# protoslice.net
KiCad netlist of a schematic drawn in EAGLE
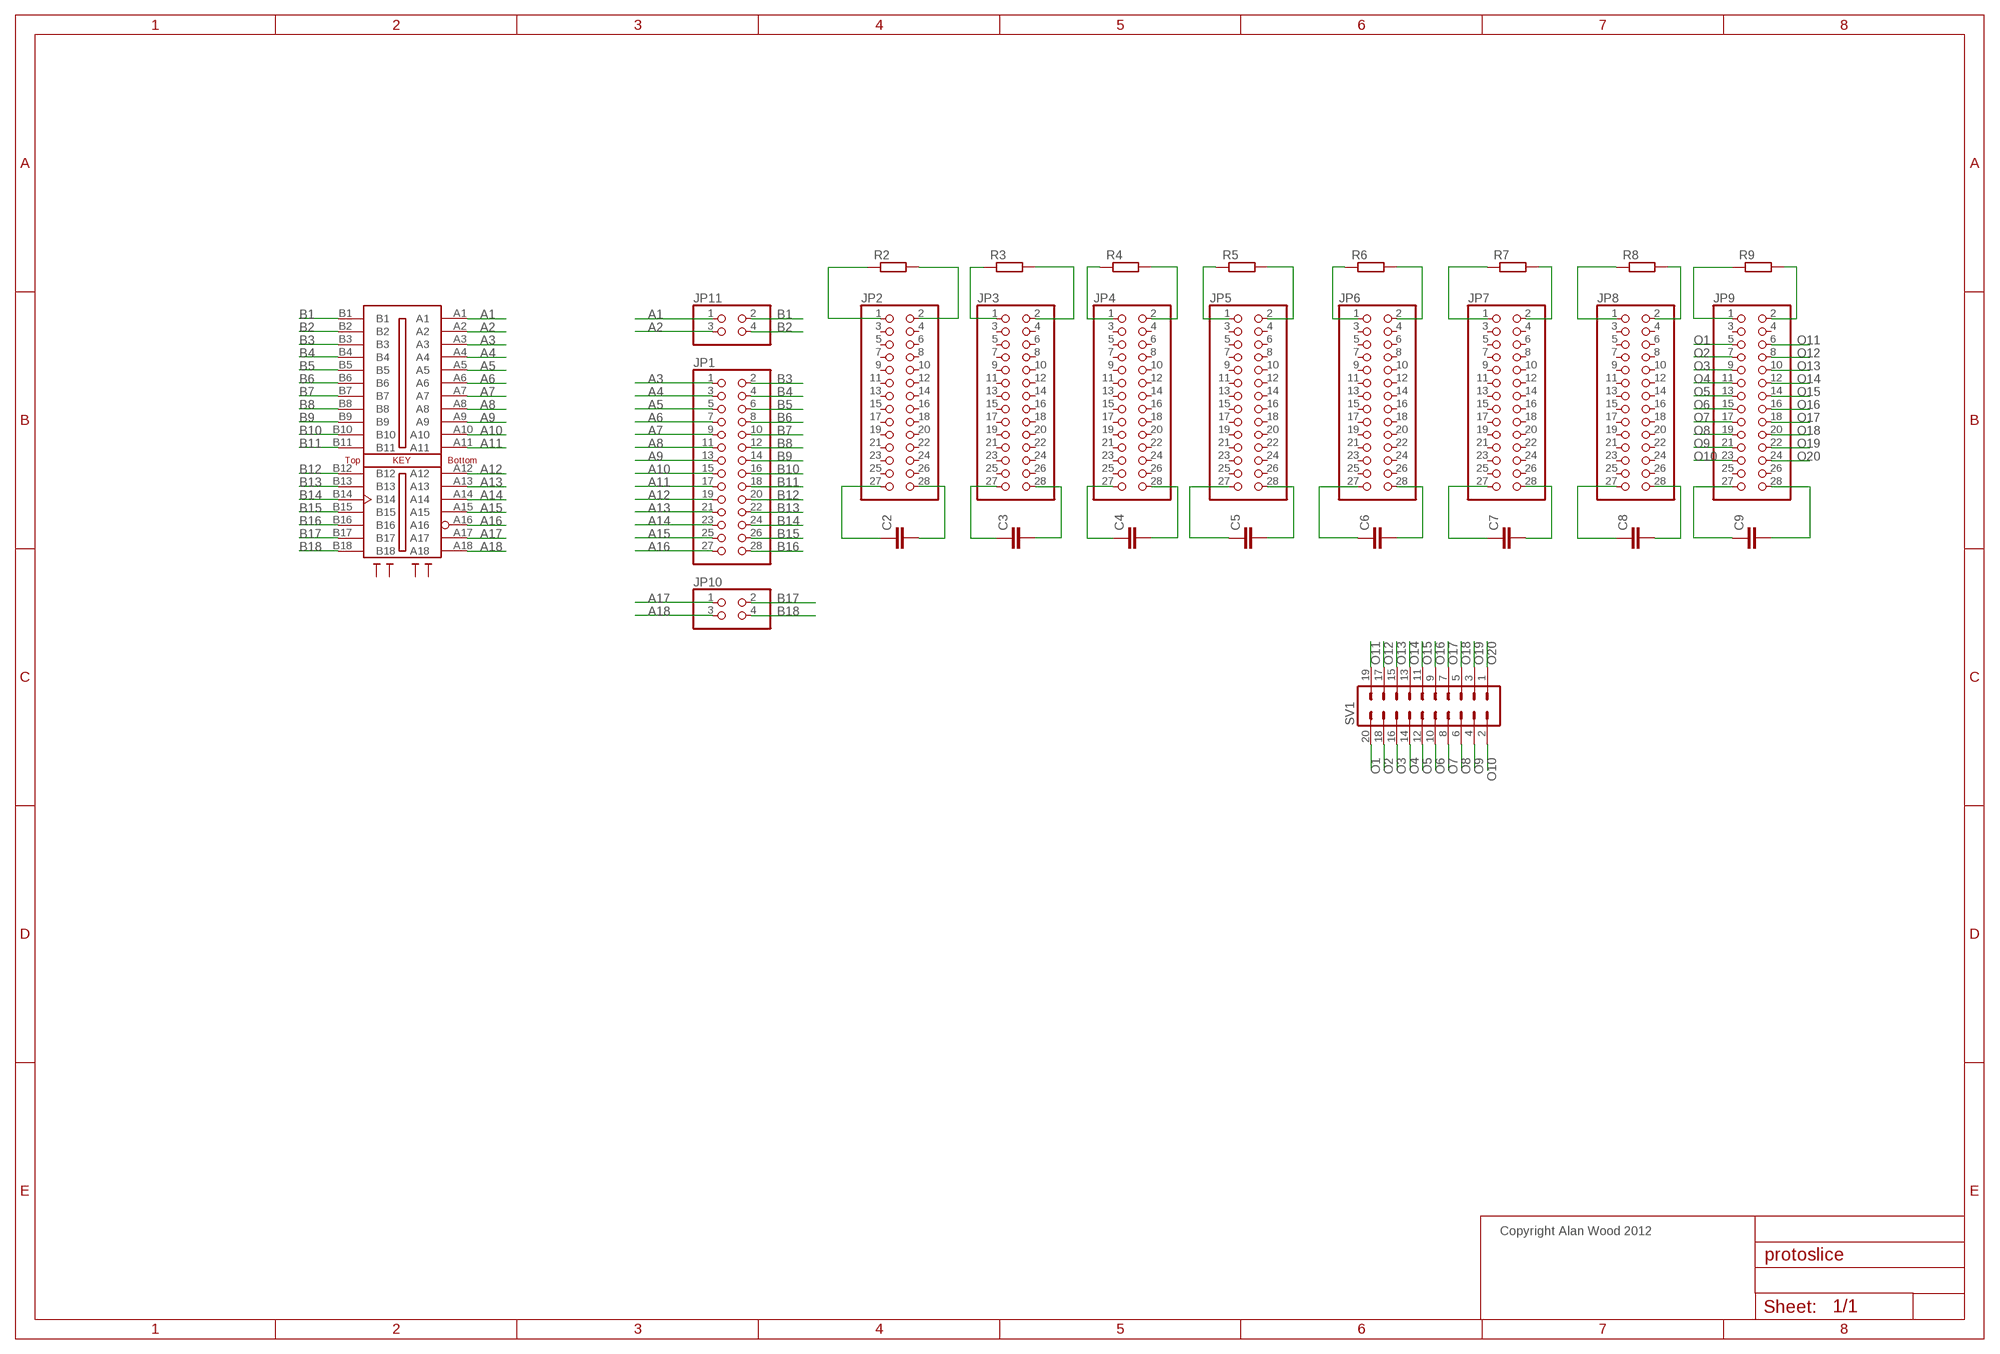
[diagram p0: schematic, sheet 1]

(export (version "E")
  (design (tool "Eeschema 10.0.6"))
  (components
    (comp (ref "C2")
      (value "C-EUC0805")
      (footprint "eagle-import:C0805")
      (libsource (lib "eagle-import") (part "C-EUC0805"))
    )
    (comp (ref "C3")
      (value "C-EUC0805")
      (footprint "eagle-import:C0805")
      (libsource (lib "eagle-import") (part "C-EUC0805"))
    )
    (comp (ref "C4")
      (value "C-EUC0805")
      (footprint "eagle-import:C0805")
      (libsource (lib "eagle-import") (part "C-EUC0805"))
    )
    (comp (ref "C5")
      (value "C-EUC0805")
      (footprint "eagle-import:C0805")
      (libsource (lib "eagle-import") (part "C-EUC0805"))
    )
    (comp (ref "C6")
      (value "C-EUC0805")
      (footprint "eagle-import:C0805")
      (libsource (lib "eagle-import") (part "C-EUC0805"))
    )
    (comp (ref "C7")
      (value "C-EUC0805")
      (footprint "eagle-import:C0805")
      (libsource (lib "eagle-import") (part "C-EUC0805"))
    )
    (comp (ref "C8")
      (value "C-EUC0805")
      (footprint "eagle-import:C0805")
      (libsource (lib "eagle-import") (part "C-EUC0805"))
    )
    (comp (ref "C9")
      (value "C-EUC0805")
      (footprint "eagle-import:C0805")
      (libsource (lib "eagle-import") (part "C-EUC0805"))
    )
    (comp (ref "JP1")
      (value "PINHD-2X14")
      (footprint "eagle-import:2X14")
      (libsource (lib "eagle-import") (part "PINHD-2X14"))
    )
    (comp (ref "JP2")
      (value "PINHD-2X14")
      (footprint "eagle-import:2X14")
      (libsource (lib "eagle-import") (part "PINHD-2X14"))
    )
    (comp (ref "JP3")
      (value "PINHD-2X14")
      (footprint "eagle-import:2X14")
      (libsource (lib "eagle-import") (part "PINHD-2X14"))
    )
    (comp (ref "JP4")
      (value "PINHD-2X14")
      (footprint "eagle-import:2X14")
      (libsource (lib "eagle-import") (part "PINHD-2X14"))
    )
    (comp (ref "JP5")
      (value "PINHD-2X14")
      (footprint "eagle-import:2X14")
      (libsource (lib "eagle-import") (part "PINHD-2X14"))
    )
    (comp (ref "JP6")
      (value "PINHD-2X14")
      (footprint "eagle-import:2X14")
      (libsource (lib "eagle-import") (part "PINHD-2X14"))
    )
    (comp (ref "JP7")
      (value "PINHD-2X14")
      (footprint "eagle-import:2X14")
      (libsource (lib "eagle-import") (part "PINHD-2X14"))
    )
    (comp (ref "JP8")
      (value "PINHD-2X14")
      (footprint "eagle-import:2X14")
      (libsource (lib "eagle-import") (part "PINHD-2X14"))
    )
    (comp (ref "JP9")
      (value "PINHD-2X14")
      (footprint "eagle-import:2X14")
      (libsource (lib "eagle-import") (part "PINHD-2X14"))
    )
    (comp (ref "JP10")
      (value "PINHD-2X2")
      (footprint "eagle-import:2X02")
      (libsource (lib "eagle-import") (part "PINHD-2X2"))
    )
    (comp (ref "JP11")
      (value "PINHD-2X2")
      (footprint "eagle-import:2X02")
      (libsource (lib "eagle-import") (part "PINHD-2X2"))
    )
    (comp (ref "R2")
      (value "R-EU_R0805")
      (footprint "eagle-import:R0805")
      (libsource (lib "eagle-import") (part "R-EU_R0805"))
    )
    (comp (ref "R3")
      (value "R-EU_R0805")
      (footprint "eagle-import:R0805")
      (libsource (lib "eagle-import") (part "R-EU_R0805"))
    )
    (comp (ref "R4")
      (value "R-EU_R0805")
      (footprint "eagle-import:R0805")
      (libsource (lib "eagle-import") (part "R-EU_R0805"))
    )
    (comp (ref "R5")
      (value "R-EU_R0805")
      (footprint "eagle-import:R0805")
      (libsource (lib "eagle-import") (part "R-EU_R0805"))
    )
    (comp (ref "R6")
      (value "R-EU_R0805")
      (footprint "eagle-import:R0805")
      (libsource (lib "eagle-import") (part "R-EU_R0805"))
    )
    (comp (ref "R7")
      (value "R-EU_R0805")
      (footprint "eagle-import:R0805")
      (libsource (lib "eagle-import") (part "R-EU_R0805"))
    )
    (comp (ref "R8")
      (value "R-EU_R0805")
      (footprint "eagle-import:R0805")
      (libsource (lib "eagle-import") (part "R-EU_R0805"))
    )
    (comp (ref "R9")
      (value "R-EU_R0805")
      (footprint "eagle-import:R0805")
      (libsource (lib "eagle-import") (part "R-EU_R0805"))
    )
    (comp (ref "SV1")
      (value "MA10-2W")
      (footprint "eagle-import:MA10-2W")
      (libsource (lib "eagle-import") (part "MA10-2W"))
    )
    (comp (ref "U$1")
      (value "XSLICE")
      (footprint "eagle-import:XSLICE")
      (libsource (lib "eagle-import") (part "XSLICE"))
    )
  )
  (nets
    (net (code "1") (name "/A1") (class "Default")
      (node (ref "JP11") (pin "1") (pinfunction "1_1") (pintype "passive"))
      (node (ref "U$1") (pin "A1") (pinfunction "A1_A1") (pintype "bidirectional"))
    )
    (net (code "2") (name "/A2") (class "Default")
      (node (ref "JP11") (pin "3") (pinfunction "3_3") (pintype "passive"))
      (node (ref "U$1") (pin "A2") (pinfunction "A2_A2") (pintype "power_in"))
    )
    (net (code "3") (name "/A3") (class "Default")
      (node (ref "JP1") (pin "1") (pinfunction "1_1") (pintype "passive"))
      (node (ref "U$1") (pin "A3") (pinfunction "A3_A3") (pintype "bidirectional"))
    )
    (net (code "4") (name "/A4") (class "Default")
      (node (ref "JP1") (pin "3") (pinfunction "3_3") (pintype "passive"))
      (node (ref "U$1") (pin "A4") (pinfunction "A4_A4") (pintype "bidirectional"))
    )
    (net (code "5") (name "/A5") (class "Default")
      (node (ref "JP1") (pin "5") (pinfunction "5_5") (pintype "passive"))
      (node (ref "U$1") (pin "A5") (pinfunction "A5_A5") (pintype "bidirectional"))
    )
    (net (code "6") (name "/A6") (class "Default")
      (node (ref "JP1") (pin "7") (pinfunction "7_7") (pintype "passive"))
      (node (ref "U$1") (pin "A6") (pinfunction "A6_A6") (pintype "bidirectional"))
    )
    (net (code "7") (name "/A7") (class "Default")
      (node (ref "JP1") (pin "9") (pinfunction "9_9") (pintype "passive"))
      (node (ref "U$1") (pin "A7") (pinfunction "A7_A7") (pintype "bidirectional"))
    )
    (net (code "8") (name "/A8") (class "Default")
      (node (ref "JP1") (pin "11") (pinfunction "11_11") (pintype "passive"))
      (node (ref "U$1") (pin "A8") (pinfunction "A8_A8") (pintype "bidirectional"))
    )
    (net (code "9") (name "/A9") (class "Default")
      (node (ref "JP1") (pin "13") (pinfunction "13_13") (pintype "passive"))
      (node (ref "U$1") (pin "A9") (pinfunction "A9_A9") (pintype "bidirectional"))
    )
    (net (code "10") (name "/A10") (class "Default")
      (node (ref "JP1") (pin "15") (pinfunction "15_15") (pintype "passive"))
      (node (ref "U$1") (pin "A10") (pinfunction "A10_A10") (pintype "power_in"))
    )
    (net (code "11") (name "/A11") (class "Default")
      (node (ref "JP1") (pin "17") (pinfunction "17_17") (pintype "passive"))
      (node (ref "U$1") (pin "A11") (pinfunction "A11_A11") (pintype "bidirectional"))
    )
    (net (code "12") (name "/A12") (class "Default")
      (node (ref "JP1") (pin "19") (pinfunction "19_19") (pintype "passive"))
      (node (ref "U$1") (pin "A12") (pinfunction "A12_A12") (pintype "bidirectional"))
    )
    (net (code "13") (name "/A13") (class "Default")
      (node (ref "JP1") (pin "21") (pinfunction "21_21") (pintype "passive"))
      (node (ref "U$1") (pin "A13") (pinfunction "A13_A13") (pintype "bidirectional"))
    )
    (net (code "14") (name "/A14") (class "Default")
      (node (ref "JP1") (pin "23") (pinfunction "23_23") (pintype "passive"))
      (node (ref "U$1") (pin "A14") (pinfunction "A14_A14") (pintype "power_in"))
    )
    (net (code "15") (name "/A15") (class "Default")
      (node (ref "JP1") (pin "25") (pinfunction "25_25") (pintype "passive"))
      (node (ref "U$1") (pin "A15") (pinfunction "A15_A15") (pintype "bidirectional"))
    )
    (net (code "16") (name "/A16") (class "Default")
      (node (ref "JP1") (pin "27") (pinfunction "27_27") (pintype "passive"))
      (node (ref "U$1") (pin "A16") (pinfunction "A16_A16") (pintype "output"))
    )
    (net (code "17") (name "/A17") (class "Default")
      (node (ref "JP10") (pin "1") (pinfunction "1_1") (pintype "passive"))
      (node (ref "U$1") (pin "A17") (pinfunction "A17_A17") (pintype "bidirectional"))
    )
    (net (code "18") (name "/A18") (class "Default")
      (node (ref "JP10") (pin "3") (pinfunction "3_3") (pintype "passive"))
      (node (ref "U$1") (pin "A18") (pinfunction "A18_A18") (pintype "bidirectional"))
    )
    (net (code "19") (name "/B1") (class "Default")
      (node (ref "JP11") (pin "2") (pinfunction "2_2") (pintype "passive"))
      (node (ref "U$1") (pin "B1") (pinfunction "B1_B1") (pintype "bidirectional"))
    )
    (net (code "20") (name "/B2") (class "Default")
      (node (ref "JP11") (pin "4") (pinfunction "4_4") (pintype "passive"))
      (node (ref "U$1") (pin "B2") (pinfunction "B2_B2") (pintype "bidirectional"))
    )
    (net (code "21") (name "/B3") (class "Default")
      (node (ref "JP1") (pin "2") (pinfunction "2_2") (pintype "passive"))
      (node (ref "U$1") (pin "B3") (pinfunction "B3_B3") (pintype "power_in"))
    )
    (net (code "22") (name "/B4") (class "Default")
      (node (ref "JP1") (pin "4") (pinfunction "4_4") (pintype "passive"))
      (node (ref "U$1") (pin "B4") (pinfunction "B4_B4") (pintype "bidirectional"))
    )
    (net (code "23") (name "/B5") (class "Default")
      (node (ref "JP1") (pin "6") (pinfunction "6_6") (pintype "passive"))
      (node (ref "U$1") (pin "B5") (pinfunction "B5_B5") (pintype "power_in"))
    )
    (net (code "24") (name "/B6") (class "Default")
      (node (ref "JP1") (pin "8") (pinfunction "8_8") (pintype "passive"))
      (node (ref "U$1") (pin "B6") (pinfunction "B6_B6") (pintype "bidirectional"))
    )
    (net (code "25") (name "/B7") (class "Default")
      (node (ref "JP1") (pin "10") (pinfunction "10_10") (pintype "passive"))
      (node (ref "U$1") (pin "B7") (pinfunction "B7_B7") (pintype "bidirectional"))
    )
    (net (code "26") (name "/B8") (class "Default")
      (node (ref "JP1") (pin "12") (pinfunction "12_12") (pintype "passive"))
      (node (ref "U$1") (pin "B8") (pinfunction "B8_B8") (pintype "power_in"))
    )
    (net (code "27") (name "/B9") (class "Default")
      (node (ref "JP1") (pin "14") (pinfunction "14_14") (pintype "passive"))
      (node (ref "U$1") (pin "B9") (pinfunction "B9_B9") (pintype "bidirectional"))
    )
    (net (code "28") (name "/B10") (class "Default")
      (node (ref "JP1") (pin "16") (pinfunction "16_16") (pintype "passive"))
      (node (ref "U$1") (pin "B10") (pinfunction "B10_B10") (pintype "bidirectional"))
    )
    (net (code "29") (name "/B11") (class "Default")
      (node (ref "JP1") (pin "18") (pinfunction "18_18") (pintype "passive"))
      (node (ref "U$1") (pin "B11") (pinfunction "B11_B11") (pintype "bidirectional"))
    )
    (net (code "30") (name "/B12") (class "Default")
      (node (ref "JP1") (pin "20") (pinfunction "20_20") (pintype "passive"))
      (node (ref "U$1") (pin "B12") (pinfunction "B12_B12") (pintype "bidirectional"))
    )
    (net (code "31") (name "/B13") (class "Default")
      (node (ref "JP1") (pin "22") (pinfunction "22_22") (pintype "passive"))
      (node (ref "U$1") (pin "B13") (pinfunction "B13_B13") (pintype "bidirectional"))
    )
    (net (code "32") (name "/B14") (class "Default")
      (node (ref "JP1") (pin "24") (pinfunction "24_24") (pintype "passive"))
      (node (ref "U$1") (pin "B14") (pinfunction "B14_B14") (pintype "output"))
    )
    (net (code "33") (name "/B15") (class "Default")
      (node (ref "JP1") (pin "26") (pinfunction "26_26") (pintype "passive"))
      (node (ref "U$1") (pin "B15") (pinfunction "B15_B15") (pintype "bidirectional"))
    )
    (net (code "34") (name "/B16") (class "Default")
      (node (ref "JP1") (pin "28") (pinfunction "28_28") (pintype "passive"))
      (node (ref "U$1") (pin "B16") (pinfunction "B16_B16") (pintype "power_in"))
    )
    (net (code "35") (name "/B17") (class "Default")
      (node (ref "JP10") (pin "2") (pinfunction "2_2") (pintype "passive"))
      (node (ref "U$1") (pin "B17") (pinfunction "B17_B17") (pintype "bidirectional"))
    )
    (net (code "36") (name "/B18") (class "Default")
      (node (ref "JP10") (pin "4") (pinfunction "4_4") (pintype "passive"))
      (node (ref "U$1") (pin "B18") (pinfunction "B18_B18") (pintype "bidirectional"))
    )
    (net (code "37") (name "/H0") (class "Default")
      (node (ref "U$1") (pin "H0") (pinfunction "H0_H0") (pintype "power_in"))
    )
    (net (code "38") (name "/H1") (class "Default")
      (node (ref "U$1") (pin "H1") (pinfunction "H1_H1") (pintype "power_in"))
    )
    (net (code "39") (name "/H2") (class "Default")
      (node (ref "U$1") (pin "H2") (pinfunction "H2_H2") (pintype "power_in"))
    )
    (net (code "40") (name "/H3") (class "Default")
      (node (ref "U$1") (pin "H3") (pinfunction "H3_H3") (pintype "power_in"))
    )
    (net (code "41") (name "/O1") (class "Default")
      (node (ref "JP9") (pin "5") (pinfunction "5_5") (pintype "passive"))
      (node (ref "SV1") (pin "20") (pinfunction "20_20") (pintype "passive"))
    )
    (net (code "42") (name "/O2") (class "Default")
      (node (ref "JP9") (pin "7") (pinfunction "7_7") (pintype "passive"))
      (node (ref "SV1") (pin "18") (pinfunction "18_18") (pintype "passive"))
    )
    (net (code "43") (name "/O3") (class "Default")
      (node (ref "JP9") (pin "9") (pinfunction "9_9") (pintype "passive"))
      (node (ref "SV1") (pin "16") (pinfunction "16_16") (pintype "passive"))
    )
    (net (code "44") (name "/O4") (class "Default")
      (node (ref "JP9") (pin "11") (pinfunction "11_11") (pintype "passive"))
      (node (ref "SV1") (pin "14") (pinfunction "14_14") (pintype "passive"))
    )
    (net (code "45") (name "/O5") (class "Default")
      (node (ref "JP9") (pin "13") (pinfunction "13_13") (pintype "passive"))
      (node (ref "SV1") (pin "12") (pinfunction "12_12") (pintype "passive"))
    )
    (net (code "46") (name "/O6") (class "Default")
      (node (ref "JP9") (pin "15") (pinfunction "15_15") (pintype "passive"))
      (node (ref "SV1") (pin "10") (pinfunction "10_10") (pintype "passive"))
    )
    (net (code "47") (name "/O7") (class "Default")
      (node (ref "JP9") (pin "17") (pinfunction "17_17") (pintype "passive"))
      (node (ref "SV1") (pin "8") (pinfunction "8_8") (pintype "passive"))
    )
    (net (code "48") (name "/O8") (class "Default")
      (node (ref "JP9") (pin "19") (pinfunction "19_19") (pintype "passive"))
      (node (ref "SV1") (pin "6") (pinfunction "6_6") (pintype "passive"))
    )
    (net (code "49") (name "/O9") (class "Default")
      (node (ref "JP9") (pin "21") (pinfunction "21_21") (pintype "passive"))
      (node (ref "SV1") (pin "4") (pinfunction "4_4") (pintype "passive"))
    )
    (net (code "50") (name "/O10") (class "Default")
      (node (ref "JP9") (pin "23") (pinfunction "23_23") (pintype "passive"))
      (node (ref "SV1") (pin "2") (pinfunction "2_2") (pintype "passive"))
    )
    (net (code "51") (name "/O11") (class "Default")
      (node (ref "JP9") (pin "6") (pinfunction "6_6") (pintype "passive"))
      (node (ref "SV1") (pin "19") (pinfunction "19_19") (pintype "passive"))
    )
    (net (code "52") (name "/O12") (class "Default")
      (node (ref "JP9") (pin "8") (pinfunction "8_8") (pintype "passive"))
      (node (ref "SV1") (pin "17") (pinfunction "17_17") (pintype "passive"))
    )
    (net (code "53") (name "/O13") (class "Default")
      (node (ref "JP9") (pin "10") (pinfunction "10_10") (pintype "passive"))
      (node (ref "SV1") (pin "15") (pinfunction "15_15") (pintype "passive"))
    )
    (net (code "54") (name "/O14") (class "Default")
      (node (ref "JP9") (pin "12") (pinfunction "12_12") (pintype "passive"))
      (node (ref "SV1") (pin "13") (pinfunction "13_13") (pintype "passive"))
    )
    (net (code "55") (name "/O15") (class "Default")
      (node (ref "JP9") (pin "14") (pinfunction "14_14") (pintype "passive"))
      (node (ref "SV1") (pin "11") (pinfunction "11_11") (pintype "passive"))
    )
    (net (code "56") (name "/O16") (class "Default")
      (node (ref "JP9") (pin "16") (pinfunction "16_16") (pintype "passive"))
      (node (ref "SV1") (pin "9") (pinfunction "9_9") (pintype "passive"))
    )
    (net (code "57") (name "/O17") (class "Default")
      (node (ref "JP9") (pin "18") (pinfunction "18_18") (pintype "passive"))
      (node (ref "SV1") (pin "7") (pinfunction "7_7") (pintype "passive"))
    )
    (net (code "58") (name "/O18") (class "Default")
      (node (ref "JP9") (pin "20") (pinfunction "20_20") (pintype "passive"))
      (node (ref "SV1") (pin "5") (pinfunction "5_5") (pintype "passive"))
    )
    (net (code "59") (name "/O19") (class "Default")
      (node (ref "JP9") (pin "22") (pinfunction "22_22") (pintype "passive"))
      (node (ref "SV1") (pin "3") (pinfunction "3_3") (pintype "passive"))
    )
    (net (code "60") (name "/O20") (class "Default")
      (node (ref "JP9") (pin "24") (pinfunction "24_24") (pintype "passive"))
      (node (ref "SV1") (pin "1") (pinfunction "1_1") (pintype "passive"))
    )
    (net (code "61") (name "Net-(C2-Pad1)") (class "Default")
      (node (ref "C2") (pin "1") (pinfunction "1_1") (pintype "passive"))
      (node (ref "JP2") (pin "27") (pinfunction "27_27") (pintype "passive"))
    )
    (net (code "62") (name "Net-(C2-Pad2)") (class "Default")
      (node (ref "C2") (pin "2") (pinfunction "2_2") (pintype "passive"))
      (node (ref "JP2") (pin "28") (pinfunction "28_28") (pintype "passive"))
    )
    (net (code "63") (name "Net-(C3-Pad1)") (class "Default")
      (node (ref "C3") (pin "1") (pinfunction "1_1") (pintype "passive"))
      (node (ref "JP3") (pin "27") (pinfunction "27_27") (pintype "passive"))
    )
    (net (code "64") (name "Net-(C3-Pad2)") (class "Default")
      (node (ref "C3") (pin "2") (pinfunction "2_2") (pintype "passive"))
      (node (ref "JP3") (pin "28") (pinfunction "28_28") (pintype "passive"))
    )
    (net (code "65") (name "Net-(C4-Pad1)") (class "Default")
      (node (ref "C4") (pin "1") (pinfunction "1_1") (pintype "passive"))
      (node (ref "JP4") (pin "27") (pinfunction "27_27") (pintype "passive"))
    )
    (net (code "66") (name "Net-(C4-Pad2)") (class "Default")
      (node (ref "C4") (pin "2") (pinfunction "2_2") (pintype "passive"))
      (node (ref "JP4") (pin "28") (pinfunction "28_28") (pintype "passive"))
    )
    (net (code "67") (name "Net-(C5-Pad1)") (class "Default")
      (node (ref "C5") (pin "1") (pinfunction "1_1") (pintype "passive"))
      (node (ref "JP5") (pin "27") (pinfunction "27_27") (pintype "passive"))
    )
    (net (code "68") (name "Net-(C5-Pad2)") (class "Default")
      (node (ref "C5") (pin "2") (pinfunction "2_2") (pintype "passive"))
      (node (ref "JP5") (pin "28") (pinfunction "28_28") (pintype "passive"))
    )
    (net (code "69") (name "Net-(C6-Pad1)") (class "Default")
      (node (ref "C6") (pin "1") (pinfunction "1_1") (pintype "passive"))
      (node (ref "JP6") (pin "27") (pinfunction "27_27") (pintype "passive"))
    )
    (net (code "70") (name "Net-(C6-Pad2)") (class "Default")
      (node (ref "C6") (pin "2") (pinfunction "2_2") (pintype "passive"))
      (node (ref "JP6") (pin "28") (pinfunction "28_28") (pintype "passive"))
    )
    (net (code "71") (name "Net-(C7-Pad1)") (class "Default")
      (node (ref "C7") (pin "1") (pinfunction "1_1") (pintype "passive"))
      (node (ref "JP7") (pin "27") (pinfunction "27_27") (pintype "passive"))
    )
    (net (code "72") (name "Net-(C7-Pad2)") (class "Default")
      (node (ref "C7") (pin "2") (pinfunction "2_2") (pintype "passive"))
      (node (ref "JP7") (pin "28") (pinfunction "28_28") (pintype "passive"))
    )
    (net (code "73") (name "Net-(C8-Pad1)") (class "Default")
      (node (ref "C8") (pin "1") (pinfunction "1_1") (pintype "passive"))
      (node (ref "JP8") (pin "27") (pinfunction "27_27") (pintype "passive"))
    )
    (net (code "74") (name "Net-(C8-Pad2)") (class "Default")
      (node (ref "C8") (pin "2") (pinfunction "2_2") (pintype "passive"))
      (node (ref "JP8") (pin "28") (pinfunction "28_28") (pintype "passive"))
    )
    (net (code "75") (name "Net-(C9-Pad1)") (class "Default")
      (node (ref "C9") (pin "1") (pinfunction "1_1") (pintype "passive"))
      (node (ref "JP9") (pin "27") (pinfunction "27_27") (pintype "passive"))
    )
    (net (code "76") (name "Net-(C9-Pad2)") (class "Default")
      (node (ref "C9") (pin "2") (pinfunction "2_2") (pintype "passive"))
      (node (ref "JP9") (pin "28") (pinfunction "28_28") (pintype "passive"))
    )
    (net (code "77") (name "Net-(JP2-Pad1)") (class "Default")
      (node (ref "JP2") (pin "1") (pinfunction "1_1") (pintype "passive"))
      (node (ref "R2") (pin "1") (pinfunction "1_1") (pintype "passive"))
    )
    (net (code "78") (name "Net-(JP2-Pad2)") (class "Default")
      (node (ref "JP2") (pin "2") (pinfunction "2_2") (pintype "passive"))
      (node (ref "R2") (pin "2") (pinfunction "2_2") (pintype "passive"))
    )
    (net (code "79") (name "Net-(JP3-Pad1)") (class "Default")
      (node (ref "JP3") (pin "1") (pinfunction "1_1") (pintype "passive"))
      (node (ref "R3") (pin "1") (pinfunction "1_1") (pintype "passive"))
    )
    (net (code "80") (name "Net-(JP3-Pad2)") (class "Default")
      (node (ref "JP3") (pin "2") (pinfunction "2_2") (pintype "passive"))
      (node (ref "R3") (pin "2") (pinfunction "2_2") (pintype "passive"))
    )
    (net (code "81") (name "Net-(JP4-Pad1)") (class "Default")
      (node (ref "JP4") (pin "1") (pinfunction "1_1") (pintype "passive"))
      (node (ref "R4") (pin "1") (pinfunction "1_1") (pintype "passive"))
    )
    (net (code "82") (name "Net-(JP4-Pad2)") (class "Default")
      (node (ref "JP4") (pin "2") (pinfunction "2_2") (pintype "passive"))
      (node (ref "R4") (pin "2") (pinfunction "2_2") (pintype "passive"))
    )
    (net (code "83") (name "Net-(JP5-Pad1)") (class "Default")
      (node (ref "JP5") (pin "1") (pinfunction "1_1") (pintype "passive"))
      (node (ref "R5") (pin "1") (pinfunction "1_1") (pintype "passive"))
    )
    (net (code "84") (name "Net-(JP5-Pad2)") (class "Default")
      (node (ref "JP5") (pin "2") (pinfunction "2_2") (pintype "passive"))
      (node (ref "R5") (pin "2") (pinfunction "2_2") (pintype "passive"))
    )
    (net (code "85") (name "Net-(JP6-Pad1)") (class "Default")
      (node (ref "JP6") (pin "1") (pinfunction "1_1") (pintype "passive"))
      (node (ref "R6") (pin "1") (pinfunction "1_1") (pintype "passive"))
    )
    (net (code "86") (name "Net-(JP6-Pad2)") (class "Default")
      (node (ref "JP6") (pin "2") (pinfunction "2_2") (pintype "passive"))
      (node (ref "R6") (pin "2") (pinfunction "2_2") (pintype "passive"))
    )
    (net (code "87") (name "Net-(JP7-Pad1)") (class "Default")
      (node (ref "JP7") (pin "1") (pinfunction "1_1") (pintype "passive"))
      (node (ref "R7") (pin "1") (pinfunction "1_1") (pintype "passive"))
    )
    (net (code "88") (name "Net-(JP7-Pad2)") (class "Default")
      (node (ref "JP7") (pin "2") (pinfunction "2_2") (pintype "passive"))
      (node (ref "R7") (pin "2") (pinfunction "2_2") (pintype "passive"))
    )
    (net (code "89") (name "Net-(JP8-Pad1)") (class "Default")
      (node (ref "JP8") (pin "1") (pinfunction "1_1") (pintype "passive"))
      (node (ref "R8") (pin "1") (pinfunction "1_1") (pintype "passive"))
    )
    (net (code "90") (name "Net-(JP8-Pad2)") (class "Default")
      (node (ref "JP8") (pin "2") (pinfunction "2_2") (pintype "passive"))
      (node (ref "R8") (pin "2") (pinfunction "2_2") (pintype "passive"))
    )
    (net (code "91") (name "Net-(JP9-Pad1)") (class "Default")
      (node (ref "JP9") (pin "1") (pinfunction "1_1") (pintype "passive"))
      (node (ref "R9") (pin "1") (pinfunction "1_1") (pintype "passive"))
    )
    (net (code "92") (name "Net-(JP9-Pad2)") (class "Default")
      (node (ref "JP9") (pin "2") (pinfunction "2_2") (pintype "passive"))
      (node (ref "R9") (pin "2") (pinfunction "2_2") (pintype "passive"))
    )
    (net (code "93") (name "unconnected-(JP2-Pad3)") (class "Default")
      (node (ref "JP2") (pin "3") (pinfunction "3_3") (pintype "passive"))
    )
    (net (code "94") (name "unconnected-(JP2-Pad4)") (class "Default")
      (node (ref "JP2") (pin "4") (pinfunction "4_4") (pintype "passive"))
    )
    (net (code "95") (name "unconnected-(JP2-Pad5)") (class "Default")
      (node (ref "JP2") (pin "5") (pinfunction "5_5") (pintype "passive"))
    )
    (net (code "96") (name "unconnected-(JP2-Pad6)") (class "Default")
      (node (ref "JP2") (pin "6") (pinfunction "6_6") (pintype "passive"))
    )
    (net (code "97") (name "unconnected-(JP2-Pad7)") (class "Default")
      (node (ref "JP2") (pin "7") (pinfunction "7_7") (pintype "passive"))
    )
    (net (code "98") (name "unconnected-(JP2-Pad8)") (class "Default")
      (node (ref "JP2") (pin "8") (pinfunction "8_8") (pintype "passive"))
    )
    (net (code "99") (name "unconnected-(JP2-Pad9)") (class "Default")
      (node (ref "JP2") (pin "9") (pinfunction "9_9") (pintype "passive"))
    )
    (net (code "100") (name "unconnected-(JP2-Pad10)") (class "Default")
      (node (ref "JP2") (pin "10") (pinfunction "10_10") (pintype "passive"))
    )
    (net (code "101") (name "unconnected-(JP2-Pad11)") (class "Default")
      (node (ref "JP2") (pin "11") (pinfunction "11_11") (pintype "passive"))
    )
    (net (code "102") (name "unconnected-(JP2-Pad12)") (class "Default")
      (node (ref "JP2") (pin "12") (pinfunction "12_12") (pintype "passive"))
    )
    (net (code "103") (name "unconnected-(JP2-Pad13)") (class "Default")
      (node (ref "JP2") (pin "13") (pinfunction "13_13") (pintype "passive"))
    )
    (net (code "104") (name "unconnected-(JP2-Pad14)") (class "Default")
      (node (ref "JP2") (pin "14") (pinfunction "14_14") (pintype "passive"))
    )
    (net (code "105") (name "unconnected-(JP2-Pad15)") (class "Default")
      (node (ref "JP2") (pin "15") (pinfunction "15_15") (pintype "passive"))
    )
    (net (code "106") (name "unconnected-(JP2-Pad16)") (class "Default")
      (node (ref "JP2") (pin "16") (pinfunction "16_16") (pintype "passive"))
    )
    (net (code "107") (name "unconnected-(JP2-Pad17)") (class "Default")
      (node (ref "JP2") (pin "17") (pinfunction "17_17") (pintype "passive"))
    )
    (net (code "108") (name "unconnected-(JP2-Pad18)") (class "Default")
      (node (ref "JP2") (pin "18") (pinfunction "18_18") (pintype "passive"))
    )
    (net (code "109") (name "unconnected-(JP2-Pad19)") (class "Default")
      (node (ref "JP2") (pin "19") (pinfunction "19_19") (pintype "passive"))
    )
    (net (code "110") (name "unconnected-(JP2-Pad20)") (class "Default")
      (node (ref "JP2") (pin "20") (pinfunction "20_20") (pintype "passive"))
    )
    (net (code "111") (name "unconnected-(JP2-Pad21)") (class "Default")
      (node (ref "JP2") (pin "21") (pinfunction "21_21") (pintype "passive"))
    )
    (net (code "112") (name "unconnected-(JP2-Pad22)") (class "Default")
      (node (ref "JP2") (pin "22") (pinfunction "22_22") (pintype "passive"))
    )
    (net (code "113") (name "unconnected-(JP2-Pad23)") (class "Default")
      (node (ref "JP2") (pin "23") (pinfunction "23_23") (pintype "passive"))
    )
    (net (code "114") (name "unconnected-(JP2-Pad24)") (class "Default")
      (node (ref "JP2") (pin "24") (pinfunction "24_24") (pintype "passive"))
    )
    (net (code "115") (name "unconnected-(JP2-Pad25)") (class "Default")
      (node (ref "JP2") (pin "25") (pinfunction "25_25") (pintype "passive"))
    )
    (net (code "116") (name "unconnected-(JP2-Pad26)") (class "Default")
      (node (ref "JP2") (pin "26") (pinfunction "26_26") (pintype "passive"))
    )
    (net (code "117") (name "unconnected-(JP3-Pad3)") (class "Default")
      (node (ref "JP3") (pin "3") (pinfunction "3_3") (pintype "passive"))
    )
    (net (code "118") (name "unconnected-(JP3-Pad4)") (class "Default")
      (node (ref "JP3") (pin "4") (pinfunction "4_4") (pintype "passive"))
    )
    (net (code "119") (name "unconnected-(JP3-Pad5)") (class "Default")
      (node (ref "JP3") (pin "5") (pinfunction "5_5") (pintype "passive"))
    )
    (net (code "120") (name "unconnected-(JP3-Pad6)") (class "Default")
      (node (ref "JP3") (pin "6") (pinfunction "6_6") (pintype "passive"))
    )
    (net (code "121") (name "unconnected-(JP3-Pad7)") (class "Default")
      (node (ref "JP3") (pin "7") (pinfunction "7_7") (pintype "passive"))
    )
    (net (code "122") (name "unconnected-(JP3-Pad8)") (class "Default")
      (node (ref "JP3") (pin "8") (pinfunction "8_8") (pintype "passive"))
    )
    (net (code "123") (name "unconnected-(JP3-Pad9)") (class "Default")
      (node (ref "JP3") (pin "9") (pinfunction "9_9") (pintype "passive"))
    )
    (net (code "124") (name "unconnected-(JP3-Pad10)") (class "Default")
      (node (ref "JP3") (pin "10") (pinfunction "10_10") (pintype "passive"))
    )
    (net (code "125") (name "unconnected-(JP3-Pad11)") (class "Default")
      (node (ref "JP3") (pin "11") (pinfunction "11_11") (pintype "passive"))
    )
    (net (code "126") (name "unconnected-(JP3-Pad12)") (class "Default")
      (node (ref "JP3") (pin "12") (pinfunction "12_12") (pintype "passive"))
    )
    (net (code "127") (name "unconnected-(JP3-Pad13)") (class "Default")
      (node (ref "JP3") (pin "13") (pinfunction "13_13") (pintype "passive"))
    )
    (net (code "128") (name "unconnected-(JP3-Pad14)") (class "Default")
      (node (ref "JP3") (pin "14") (pinfunction "14_14") (pintype "passive"))
    )
    (net (code "129") (name "unconnected-(JP3-Pad15)") (class "Default")
      (node (ref "JP3") (pin "15") (pinfunction "15_15") (pintype "passive"))
    )
    (net (code "130") (name "unconnected-(JP3-Pad16)") (class "Default")
      (node (ref "JP3") (pin "16") (pinfunction "16_16") (pintype "passive"))
    )
    (net (code "131") (name "unconnected-(JP3-Pad17)") (class "Default")
      (node (ref "JP3") (pin "17") (pinfunction "17_17") (pintype "passive"))
    )
    (net (code "132") (name "unconnected-(JP3-Pad18)") (class "Default")
      (node (ref "JP3") (pin "18") (pinfunction "18_18") (pintype "passive"))
    )
    (net (code "133") (name "unconnected-(JP3-Pad19)") (class "Default")
      (node (ref "JP3") (pin "19") (pinfunction "19_19") (pintype "passive"))
    )
    (net (code "134") (name "unconnected-(JP3-Pad20)") (class "Default")
      (node (ref "JP3") (pin "20") (pinfunction "20_20") (pintype "passive"))
    )
    (net (code "135") (name "unconnected-(JP3-Pad21)") (class "Default")
      (node (ref "JP3") (pin "21") (pinfunction "21_21") (pintype "passive"))
    )
    (net (code "136") (name "unconnected-(JP3-Pad22)") (class "Default")
      (node (ref "JP3") (pin "22") (pinfunction "22_22") (pintype "passive"))
    )
    (net (code "137") (name "unconnected-(JP3-Pad23)") (class "Default")
      (node (ref "JP3") (pin "23") (pinfunction "23_23") (pintype "passive"))
    )
    (net (code "138") (name "unconnected-(JP3-Pad24)") (class "Default")
      (node (ref "JP3") (pin "24") (pinfunction "24_24") (pintype "passive"))
    )
    (net (code "139") (name "unconnected-(JP3-Pad25)") (class "Default")
      (node (ref "JP3") (pin "25") (pinfunction "25_25") (pintype "passive"))
    )
    (net (code "140") (name "unconnected-(JP3-Pad26)") (class "Default")
      (node (ref "JP3") (pin "26") (pinfunction "26_26") (pintype "passive"))
    )
    (net (code "141") (name "unconnected-(JP4-Pad3)") (class "Default")
      (node (ref "JP4") (pin "3") (pinfunction "3_3") (pintype "passive"))
    )
    (net (code "142") (name "unconnected-(JP4-Pad4)") (class "Default")
      (node (ref "JP4") (pin "4") (pinfunction "4_4") (pintype "passive"))
    )
    (net (code "143") (name "unconnected-(JP4-Pad5)") (class "Default")
      (node (ref "JP4") (pin "5") (pinfunction "5_5") (pintype "passive"))
    )
    (net (code "144") (name "unconnected-(JP4-Pad6)") (class "Default")
      (node (ref "JP4") (pin "6") (pinfunction "6_6") (pintype "passive"))
    )
    (net (code "145") (name "unconnected-(JP4-Pad7)") (class "Default")
      (node (ref "JP4") (pin "7") (pinfunction "7_7") (pintype "passive"))
    )
    (net (code "146") (name "unconnected-(JP4-Pad8)") (class "Default")
      (node (ref "JP4") (pin "8") (pinfunction "8_8") (pintype "passive"))
    )
    (net (code "147") (name "unconnected-(JP4-Pad9)") (class "Default")
      (node (ref "JP4") (pin "9") (pinfunction "9_9") (pintype "passive"))
    )
    (net (code "148") (name "unconnected-(JP4-Pad10)") (class "Default")
      (node (ref "JP4") (pin "10") (pinfunction "10_10") (pintype "passive"))
    )
    (net (code "149") (name "unconnected-(JP4-Pad11)") (class "Default")
      (node (ref "JP4") (pin "11") (pinfunction "11_11") (pintype "passive"))
    )
    (net (code "150") (name "unconnected-(JP4-Pad12)") (class "Default")
      (node (ref "JP4") (pin "12") (pinfunction "12_12") (pintype "passive"))
    )
    (net (code "151") (name "unconnected-(JP4-Pad13)") (class "Default")
      (node (ref "JP4") (pin "13") (pinfunction "13_13") (pintype "passive"))
    )
    (net (code "152") (name "unconnected-(JP4-Pad14)") (class "Default")
      (node (ref "JP4") (pin "14") (pinfunction "14_14") (pintype "passive"))
    )
    (net (code "153") (name "unconnected-(JP4-Pad15)") (class "Default")
      (node (ref "JP4") (pin "15") (pinfunction "15_15") (pintype "passive"))
    )
    (net (code "154") (name "unconnected-(JP4-Pad16)") (class "Default")
      (node (ref "JP4") (pin "16") (pinfunction "16_16") (pintype "passive"))
    )
    (net (code "155") (name "unconnected-(JP4-Pad17)") (class "Default")
      (node (ref "JP4") (pin "17") (pinfunction "17_17") (pintype "passive"))
    )
    (net (code "156") (name "unconnected-(JP4-Pad18)") (class "Default")
      (node (ref "JP4") (pin "18") (pinfunction "18_18") (pintype "passive"))
    )
    (net (code "157") (name "unconnected-(JP4-Pad19)") (class "Default")
      (node (ref "JP4") (pin "19") (pinfunction "19_19") (pintype "passive"))
    )
    (net (code "158") (name "unconnected-(JP4-Pad20)") (class "Default")
      (node (ref "JP4") (pin "20") (pinfunction "20_20") (pintype "passive"))
    )
    (net (code "159") (name "unconnected-(JP4-Pad21)") (class "Default")
      (node (ref "JP4") (pin "21") (pinfunction "21_21") (pintype "passive"))
    )
    (net (code "160") (name "unconnected-(JP4-Pad22)") (class "Default")
      (node (ref "JP4") (pin "22") (pinfunction "22_22") (pintype "passive"))
    )
    (net (code "161") (name "unconnected-(JP4-Pad23)") (class "Default")
      (node (ref "JP4") (pin "23") (pinfunction "23_23") (pintype "passive"))
    )
    (net (code "162") (name "unconnected-(JP4-Pad24)") (class "Default")
      (node (ref "JP4") (pin "24") (pinfunction "24_24") (pintype "passive"))
    )
    (net (code "163") (name "unconnected-(JP4-Pad25)") (class "Default")
      (node (ref "JP4") (pin "25") (pinfunction "25_25") (pintype "passive"))
    )
    (net (code "164") (name "unconnected-(JP4-Pad26)") (class "Default")
      (node (ref "JP4") (pin "26") (pinfunction "26_26") (pintype "passive"))
    )
    (net (code "165") (name "unconnected-(JP5-Pad3)") (class "Default")
      (node (ref "JP5") (pin "3") (pinfunction "3_3") (pintype "passive"))
    )
    (net (code "166") (name "unconnected-(JP5-Pad4)") (class "Default")
      (node (ref "JP5") (pin "4") (pinfunction "4_4") (pintype "passive"))
    )
    (net (code "167") (name "unconnected-(JP5-Pad5)") (class "Default")
      (node (ref "JP5") (pin "5") (pinfunction "5_5") (pintype "passive"))
    )
    (net (code "168") (name "unconnected-(JP5-Pad6)") (class "Default")
      (node (ref "JP5") (pin "6") (pinfunction "6_6") (pintype "passive"))
    )
    (net (code "169") (name "unconnected-(JP5-Pad7)") (class "Default")
      (node (ref "JP5") (pin "7") (pinfunction "7_7") (pintype "passive"))
    )
    (net (code "170") (name "unconnected-(JP5-Pad8)") (class "Default")
      (node (ref "JP5") (pin "8") (pinfunction "8_8") (pintype "passive"))
    )
    (net (code "171") (name "unconnected-(JP5-Pad9)") (class "Default")
      (node (ref "JP5") (pin "9") (pinfunction "9_9") (pintype "passive"))
    )
    (net (code "172") (name "unconnected-(JP5-Pad10)") (class "Default")
      (node (ref "JP5") (pin "10") (pinfunction "10_10") (pintype "passive"))
    )
    (net (code "173") (name "unconnected-(JP5-Pad11)") (class "Default")
      (node (ref "JP5") (pin "11") (pinfunction "11_11") (pintype "passive"))
    )
    (net (code "174") (name "unconnected-(JP5-Pad12)") (class "Default")
      (node (ref "JP5") (pin "12") (pinfunction "12_12") (pintype "passive"))
    )
    (net (code "175") (name "unconnected-(JP5-Pad13)") (class "Default")
      (node (ref "JP5") (pin "13") (pinfunction "13_13") (pintype "passive"))
    )
    (net (code "176") (name "unconnected-(JP5-Pad14)") (class "Default")
      (node (ref "JP5") (pin "14") (pinfunction "14_14") (pintype "passive"))
    )
    (net (code "177") (name "unconnected-(JP5-Pad15)") (class "Default")
      (node (ref "JP5") (pin "15") (pinfunction "15_15") (pintype "passive"))
    )
    (net (code "178") (name "unconnected-(JP5-Pad16)") (class "Default")
      (node (ref "JP5") (pin "16") (pinfunction "16_16") (pintype "passive"))
    )
    (net (code "179") (name "unconnected-(JP5-Pad17)") (class "Default")
      (node (ref "JP5") (pin "17") (pinfunction "17_17") (pintype "passive"))
    )
    (net (code "180") (name "unconnected-(JP5-Pad18)") (class "Default")
      (node (ref "JP5") (pin "18") (pinfunction "18_18") (pintype "passive"))
    )
    (net (code "181") (name "unconnected-(JP5-Pad19)") (class "Default")
      (node (ref "JP5") (pin "19") (pinfunction "19_19") (pintype "passive"))
    )
    (net (code "182") (name "unconnected-(JP5-Pad20)") (class "Default")
      (node (ref "JP5") (pin "20") (pinfunction "20_20") (pintype "passive"))
    )
    (net (code "183") (name "unconnected-(JP5-Pad21)") (class "Default")
      (node (ref "JP5") (pin "21") (pinfunction "21_21") (pintype "passive"))
    )
    (net (code "184") (name "unconnected-(JP5-Pad22)") (class "Default")
      (node (ref "JP5") (pin "22") (pinfunction "22_22") (pintype "passive"))
    )
    (net (code "185") (name "unconnected-(JP5-Pad23)") (class "Default")
      (node (ref "JP5") (pin "23") (pinfunction "23_23") (pintype "passive"))
    )
    (net (code "186") (name "unconnected-(JP5-Pad24)") (class "Default")
      (node (ref "JP5") (pin "24") (pinfunction "24_24") (pintype "passive"))
    )
    (net (code "187") (name "unconnected-(JP5-Pad25)") (class "Default")
      (node (ref "JP5") (pin "25") (pinfunction "25_25") (pintype "passive"))
    )
    (net (code "188") (name "unconnected-(JP5-Pad26)") (class "Default")
      (node (ref "JP5") (pin "26") (pinfunction "26_26") (pintype "passive"))
    )
    (net (code "189") (name "unconnected-(JP6-Pad3)") (class "Default")
      (node (ref "JP6") (pin "3") (pinfunction "3_3") (pintype "passive"))
    )
    (net (code "190") (name "unconnected-(JP6-Pad4)") (class "Default")
      (node (ref "JP6") (pin "4") (pinfunction "4_4") (pintype "passive"))
    )
    (net (code "191") (name "unconnected-(JP6-Pad5)") (class "Default")
      (node (ref "JP6") (pin "5") (pinfunction "5_5") (pintype "passive"))
    )
    (net (code "192") (name "unconnected-(JP6-Pad6)") (class "Default")
      (node (ref "JP6") (pin "6") (pinfunction "6_6") (pintype "passive"))
    )
    (net (code "193") (name "unconnected-(JP6-Pad7)") (class "Default")
      (node (ref "JP6") (pin "7") (pinfunction "7_7") (pintype "passive"))
    )
    (net (code "194") (name "unconnected-(JP6-Pad8)") (class "Default")
      (node (ref "JP6") (pin "8") (pinfunction "8_8") (pintype "passive"))
    )
    (net (code "195") (name "unconnected-(JP6-Pad9)") (class "Default")
      (node (ref "JP6") (pin "9") (pinfunction "9_9") (pintype "passive"))
    )
    (net (code "196") (name "unconnected-(JP6-Pad10)") (class "Default")
      (node (ref "JP6") (pin "10") (pinfunction "10_10") (pintype "passive"))
    )
    (net (code "197") (name "unconnected-(JP6-Pad11)") (class "Default")
      (node (ref "JP6") (pin "11") (pinfunction "11_11") (pintype "passive"))
    )
    (net (code "198") (name "unconnected-(JP6-Pad12)") (class "Default")
      (node (ref "JP6") (pin "12") (pinfunction "12_12") (pintype "passive"))
    )
    (net (code "199") (name "unconnected-(JP6-Pad13)") (class "Default")
      (node (ref "JP6") (pin "13") (pinfunction "13_13") (pintype "passive"))
    )
    (net (code "200") (name "unconnected-(JP6-Pad14)") (class "Default")
      (node (ref "JP6") (pin "14") (pinfunction "14_14") (pintype "passive"))
    )
    (net (code "201") (name "unconnected-(JP6-Pad15)") (class "Default")
      (node (ref "JP6") (pin "15") (pinfunction "15_15") (pintype "passive"))
    )
    (net (code "202") (name "unconnected-(JP6-Pad16)") (class "Default")
      (node (ref "JP6") (pin "16") (pinfunction "16_16") (pintype "passive"))
    )
    (net (code "203") (name "unconnected-(JP6-Pad17)") (class "Default")
      (node (ref "JP6") (pin "17") (pinfunction "17_17") (pintype "passive"))
    )
    (net (code "204") (name "unconnected-(JP6-Pad18)") (class "Default")
      (node (ref "JP6") (pin "18") (pinfunction "18_18") (pintype "passive"))
    )
    (net (code "205") (name "unconnected-(JP6-Pad19)") (class "Default")
      (node (ref "JP6") (pin "19") (pinfunction "19_19") (pintype "passive"))
    )
    (net (code "206") (name "unconnected-(JP6-Pad20)") (class "Default")
      (node (ref "JP6") (pin "20") (pinfunction "20_20") (pintype "passive"))
    )
    (net (code "207") (name "unconnected-(JP6-Pad21)") (class "Default")
      (node (ref "JP6") (pin "21") (pinfunction "21_21") (pintype "passive"))
    )
    (net (code "208") (name "unconnected-(JP6-Pad22)") (class "Default")
      (node (ref "JP6") (pin "22") (pinfunction "22_22") (pintype "passive"))
    )
    (net (code "209") (name "unconnected-(JP6-Pad23)") (class "Default")
      (node (ref "JP6") (pin "23") (pinfunction "23_23") (pintype "passive"))
    )
    (net (code "210") (name "unconnected-(JP6-Pad24)") (class "Default")
      (node (ref "JP6") (pin "24") (pinfunction "24_24") (pintype "passive"))
    )
    (net (code "211") (name "unconnected-(JP6-Pad25)") (class "Default")
      (node (ref "JP6") (pin "25") (pinfunction "25_25") (pintype "passive"))
    )
    (net (code "212") (name "unconnected-(JP6-Pad26)") (class "Default")
      (node (ref "JP6") (pin "26") (pinfunction "26_26") (pintype "passive"))
    )
    (net (code "213") (name "unconnected-(JP7-Pad3)") (class "Default")
      (node (ref "JP7") (pin "3") (pinfunction "3_3") (pintype "passive"))
    )
    (net (code "214") (name "unconnected-(JP7-Pad4)") (class "Default")
      (node (ref "JP7") (pin "4") (pinfunction "4_4") (pintype "passive"))
    )
    (net (code "215") (name "unconnected-(JP7-Pad5)") (class "Default")
      (node (ref "JP7") (pin "5") (pinfunction "5_5") (pintype "passive"))
    )
    (net (code "216") (name "unconnected-(JP7-Pad6)") (class "Default")
      (node (ref "JP7") (pin "6") (pinfunction "6_6") (pintype "passive"))
    )
    (net (code "217") (name "unconnected-(JP7-Pad7)") (class "Default")
      (node (ref "JP7") (pin "7") (pinfunction "7_7") (pintype "passive"))
    )
    (net (code "218") (name "unconnected-(JP7-Pad8)") (class "Default")
      (node (ref "JP7") (pin "8") (pinfunction "8_8") (pintype "passive"))
    )
    (net (code "219") (name "unconnected-(JP7-Pad9)") (class "Default")
      (node (ref "JP7") (pin "9") (pinfunction "9_9") (pintype "passive"))
    )
    (net (code "220") (name "unconnected-(JP7-Pad10)") (class "Default")
      (node (ref "JP7") (pin "10") (pinfunction "10_10") (pintype "passive"))
    )
    (net (code "221") (name "unconnected-(JP7-Pad11)") (class "Default")
      (node (ref "JP7") (pin "11") (pinfunction "11_11") (pintype "passive"))
    )
    (net (code "222") (name "unconnected-(JP7-Pad12)") (class "Default")
      (node (ref "JP7") (pin "12") (pinfunction "12_12") (pintype "passive"))
    )
    (net (code "223") (name "unconnected-(JP7-Pad13)") (class "Default")
      (node (ref "JP7") (pin "13") (pinfunction "13_13") (pintype "passive"))
    )
    (net (code "224") (name "unconnected-(JP7-Pad14)") (class "Default")
      (node (ref "JP7") (pin "14") (pinfunction "14_14") (pintype "passive"))
    )
    (net (code "225") (name "unconnected-(JP7-Pad15)") (class "Default")
      (node (ref "JP7") (pin "15") (pinfunction "15_15") (pintype "passive"))
    )
    (net (code "226") (name "unconnected-(JP7-Pad16)") (class "Default")
      (node (ref "JP7") (pin "16") (pinfunction "16_16") (pintype "passive"))
    )
    (net (code "227") (name "unconnected-(JP7-Pad17)") (class "Default")
      (node (ref "JP7") (pin "17") (pinfunction "17_17") (pintype "passive"))
    )
    (net (code "228") (name "unconnected-(JP7-Pad18)") (class "Default")
      (node (ref "JP7") (pin "18") (pinfunction "18_18") (pintype "passive"))
    )
    (net (code "229") (name "unconnected-(JP7-Pad19)") (class "Default")
      (node (ref "JP7") (pin "19") (pinfunction "19_19") (pintype "passive"))
    )
    (net (code "230") (name "unconnected-(JP7-Pad20)") (class "Default")
      (node (ref "JP7") (pin "20") (pinfunction "20_20") (pintype "passive"))
    )
    (net (code "231") (name "unconnected-(JP7-Pad21)") (class "Default")
      (node (ref "JP7") (pin "21") (pinfunction "21_21") (pintype "passive"))
    )
    (net (code "232") (name "unconnected-(JP7-Pad22)") (class "Default")
      (node (ref "JP7") (pin "22") (pinfunction "22_22") (pintype "passive"))
    )
    (net (code "233") (name "unconnected-(JP7-Pad23)") (class "Default")
      (node (ref "JP7") (pin "23") (pinfunction "23_23") (pintype "passive"))
    )
    (net (code "234") (name "unconnected-(JP7-Pad24)") (class "Default")
      (node (ref "JP7") (pin "24") (pinfunction "24_24") (pintype "passive"))
    )
    (net (code "235") (name "unconnected-(JP7-Pad25)") (class "Default")
      (node (ref "JP7") (pin "25") (pinfunction "25_25") (pintype "passive"))
    )
    (net (code "236") (name "unconnected-(JP7-Pad26)") (class "Default")
      (node (ref "JP7") (pin "26") (pinfunction "26_26") (pintype "passive"))
    )
    (net (code "237") (name "unconnected-(JP8-Pad3)") (class "Default")
      (node (ref "JP8") (pin "3") (pinfunction "3_3") (pintype "passive"))
    )
    (net (code "238") (name "unconnected-(JP8-Pad4)") (class "Default")
      (node (ref "JP8") (pin "4") (pinfunction "4_4") (pintype "passive"))
    )
    (net (code "239") (name "unconnected-(JP8-Pad5)") (class "Default")
      (node (ref "JP8") (pin "5") (pinfunction "5_5") (pintype "passive"))
    )
    (net (code "240") (name "unconnected-(JP8-Pad6)") (class "Default")
      (node (ref "JP8") (pin "6") (pinfunction "6_6") (pintype "passive"))
    )
    (net (code "241") (name "unconnected-(JP8-Pad7)") (class "Default")
      (node (ref "JP8") (pin "7") (pinfunction "7_7") (pintype "passive"))
    )
    (net (code "242") (name "unconnected-(JP8-Pad8)") (class "Default")
      (node (ref "JP8") (pin "8") (pinfunction "8_8") (pintype "passive"))
    )
    (net (code "243") (name "unconnected-(JP8-Pad9)") (class "Default")
      (node (ref "JP8") (pin "9") (pinfunction "9_9") (pintype "passive"))
    )
    (net (code "244") (name "unconnected-(JP8-Pad10)") (class "Default")
      (node (ref "JP8") (pin "10") (pinfunction "10_10") (pintype "passive"))
    )
    (net (code "245") (name "unconnected-(JP8-Pad11)") (class "Default")
      (node (ref "JP8") (pin "11") (pinfunction "11_11") (pintype "passive"))
    )
    (net (code "246") (name "unconnected-(JP8-Pad12)") (class "Default")
      (node (ref "JP8") (pin "12") (pinfunction "12_12") (pintype "passive"))
    )
    (net (code "247") (name "unconnected-(JP8-Pad13)") (class "Default")
      (node (ref "JP8") (pin "13") (pinfunction "13_13") (pintype "passive"))
    )
    (net (code "248") (name "unconnected-(JP8-Pad14)") (class "Default")
      (node (ref "JP8") (pin "14") (pinfunction "14_14") (pintype "passive"))
    )
    (net (code "249") (name "unconnected-(JP8-Pad15)") (class "Default")
      (node (ref "JP8") (pin "15") (pinfunction "15_15") (pintype "passive"))
    )
    (net (code "250") (name "unconnected-(JP8-Pad16)") (class "Default")
      (node (ref "JP8") (pin "16") (pinfunction "16_16") (pintype "passive"))
    )
    (net (code "251") (name "unconnected-(JP8-Pad17)") (class "Default")
      (node (ref "JP8") (pin "17") (pinfunction "17_17") (pintype "passive"))
    )
    (net (code "252") (name "unconnected-(JP8-Pad18)") (class "Default")
      (node (ref "JP8") (pin "18") (pinfunction "18_18") (pintype "passive"))
    )
    (net (code "253") (name "unconnected-(JP8-Pad19)") (class "Default")
      (node (ref "JP8") (pin "19") (pinfunction "19_19") (pintype "passive"))
    )
    (net (code "254") (name "unconnected-(JP8-Pad20)") (class "Default")
      (node (ref "JP8") (pin "20") (pinfunction "20_20") (pintype "passive"))
    )
    (net (code "255") (name "unconnected-(JP8-Pad21)") (class "Default")
      (node (ref "JP8") (pin "21") (pinfunction "21_21") (pintype "passive"))
    )
    (net (code "256") (name "unconnected-(JP8-Pad22)") (class "Default")
      (node (ref "JP8") (pin "22") (pinfunction "22_22") (pintype "passive"))
    )
    (net (code "257") (name "unconnected-(JP8-Pad23)") (class "Default")
      (node (ref "JP8") (pin "23") (pinfunction "23_23") (pintype "passive"))
    )
    (net (code "258") (name "unconnected-(JP8-Pad24)") (class "Default")
      (node (ref "JP8") (pin "24") (pinfunction "24_24") (pintype "passive"))
    )
    (net (code "259") (name "unconnected-(JP8-Pad25)") (class "Default")
      (node (ref "JP8") (pin "25") (pinfunction "25_25") (pintype "passive"))
    )
    (net (code "260") (name "unconnected-(JP8-Pad26)") (class "Default")
      (node (ref "JP8") (pin "26") (pinfunction "26_26") (pintype "passive"))
    )
    (net (code "261") (name "unconnected-(JP9-Pad3)") (class "Default")
      (node (ref "JP9") (pin "3") (pinfunction "3_3") (pintype "passive"))
    )
    (net (code "262") (name "unconnected-(JP9-Pad4)") (class "Default")
      (node (ref "JP9") (pin "4") (pinfunction "4_4") (pintype "passive"))
    )
    (net (code "263") (name "unconnected-(JP9-Pad25)") (class "Default")
      (node (ref "JP9") (pin "25") (pinfunction "25_25") (pintype "passive"))
    )
    (net (code "264") (name "unconnected-(JP9-Pad26)") (class "Default")
      (node (ref "JP9") (pin "26") (pinfunction "26_26") (pintype "passive"))
    )
  )
)
